# led.net
KiCad netlist of a schematic drawn in EAGLE
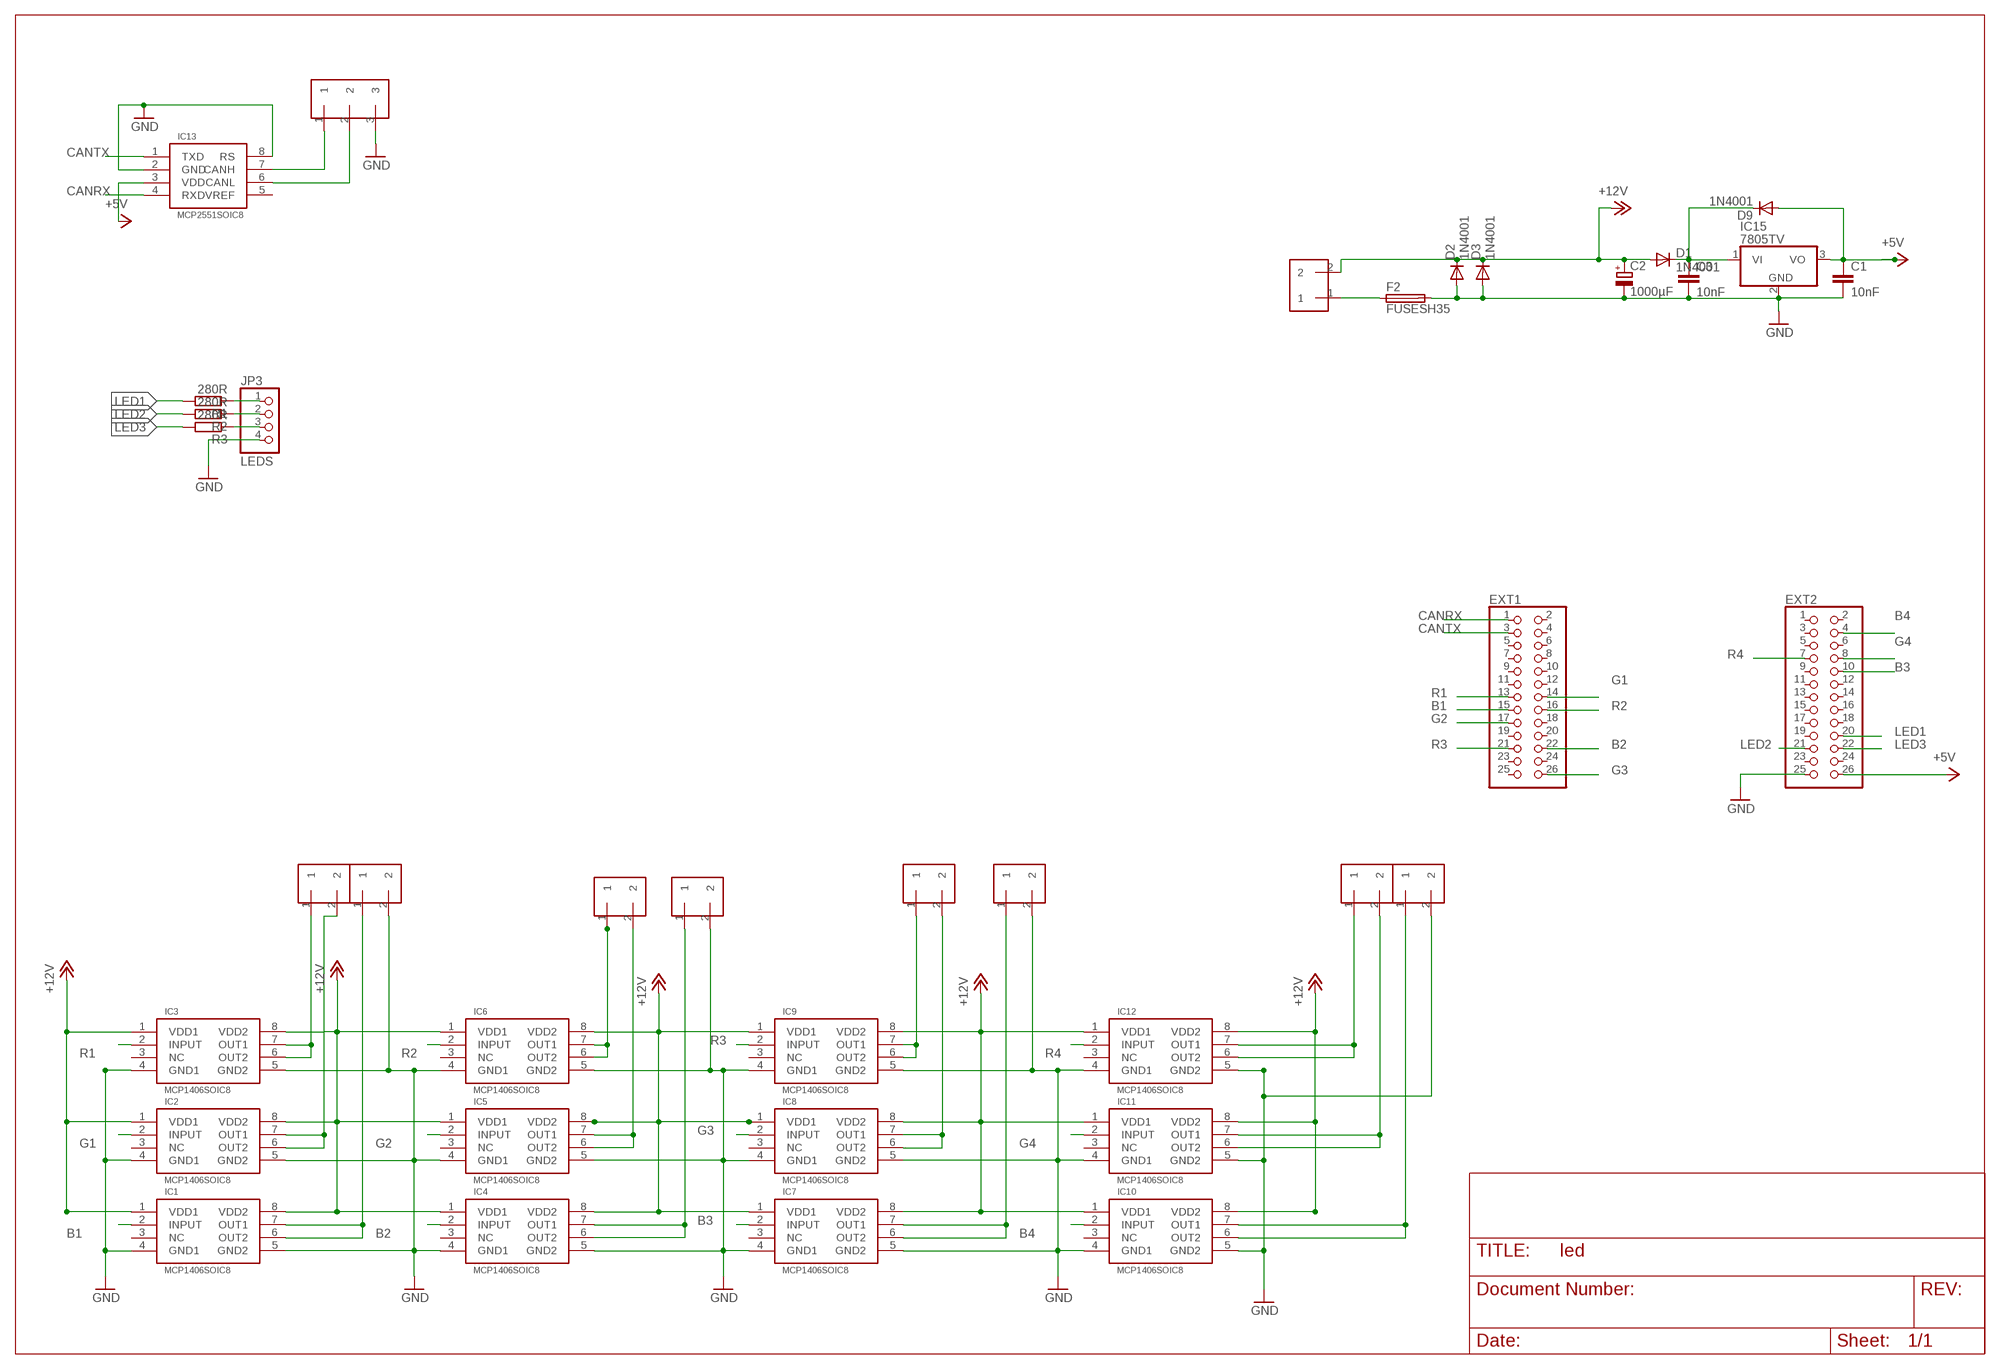
[diagram p0: schematic, sheet 1]

(export (version "E")
  (design (tool "Eeschema 10.0.6"))
  (components
    (comp (ref "C1")
      (value "10nF")
      (footprint "eagle-import:C025-025X050")
      (libsource (lib "eagle-import") (part "C-EU025-025X050"))
    )
    (comp (ref "C2")
      (value "1000µF")
      (footprint "eagle-import:E5-8,5")
      (libsource (lib "eagle-import") (part "CPOL-EUE5-8.5"))
    )
    (comp (ref "C3")
      (value "10nF")
      (footprint "eagle-import:C025-025X050")
      (libsource (lib "eagle-import") (part "C-EU025-025X050"))
    )
    (comp (ref "D1")
      (value "1N4001")
      (footprint "eagle-import:MELF-MLL41")
      (libsource (lib "eagle-import") (part "DIODE-MELF-MLL41"))
    )
    (comp (ref "D2")
      (value "1N4001")
      (footprint "eagle-import:MELF-MLL41")
      (libsource (lib "eagle-import") (part "DIODE-MELF-MLL41"))
    )
    (comp (ref "D3")
      (value "1N4001")
      (footprint "eagle-import:MELF-MLL41")
      (libsource (lib "eagle-import") (part "DIODE-MELF-MLL41"))
    )
    (comp (ref "D9")
      (value "1N4001")
      (footprint "eagle-import:MELF-MLL41")
      (libsource (lib "eagle-import") (part "DIODE-MELF-MLL41"))
    )
    (comp (ref "EXT1")
      (value "PINHD-2X13")
      (footprint "eagle-import:2X13")
      (libsource (lib "eagle-import") (part "PINHD-2X13"))
    )
    (comp (ref "EXT2")
      (value "PINHD-2X13")
      (footprint "eagle-import:2X13")
      (libsource (lib "eagle-import") (part "PINHD-2X13"))
    )
    (comp (ref "F2")
      (value "FUSESH35")
      (footprint "eagle-import:SH25")
      (libsource (lib "eagle-import") (part "FUSESH35"))
    )
    (comp (ref "IC1")
      (value "MCP1406SOIC8")
      (footprint "eagle-import:SOIC-08LG")
      (libsource (lib "eagle-import") (part "MCP1406SOIC8"))
    )
    (comp (ref "IC2")
      (value "MCP1406SOIC8")
      (footprint "eagle-import:SOIC-08LG")
      (libsource (lib "eagle-import") (part "MCP1406SOIC8"))
    )
    (comp (ref "IC3")
      (value "MCP1406SOIC8")
      (footprint "eagle-import:SOIC-08LG")
      (libsource (lib "eagle-import") (part "MCP1406SOIC8"))
    )
    (comp (ref "IC4")
      (value "MCP1406SOIC8")
      (footprint "eagle-import:SOIC-08LG")
      (libsource (lib "eagle-import") (part "MCP1406SOIC8"))
    )
    (comp (ref "IC5")
      (value "MCP1406SOIC8")
      (footprint "eagle-import:SOIC-08LG")
      (libsource (lib "eagle-import") (part "MCP1406SOIC8"))
    )
    (comp (ref "IC6")
      (value "MCP1406SOIC8")
      (footprint "eagle-import:SOIC-08LG")
      (libsource (lib "eagle-import") (part "MCP1406SOIC8"))
    )
    (comp (ref "IC7")
      (value "MCP1406SOIC8")
      (footprint "eagle-import:SOIC-08LG")
      (libsource (lib "eagle-import") (part "MCP1406SOIC8"))
    )
    (comp (ref "IC8")
      (value "MCP1406SOIC8")
      (footprint "eagle-import:SOIC-08LG")
      (libsource (lib "eagle-import") (part "MCP1406SOIC8"))
    )
    (comp (ref "IC9")
      (value "MCP1406SOIC8")
      (footprint "eagle-import:SOIC-08LG")
      (libsource (lib "eagle-import") (part "MCP1406SOIC8"))
    )
    (comp (ref "IC10")
      (value "MCP1406SOIC8")
      (footprint "eagle-import:SOIC-08LG")
      (libsource (lib "eagle-import") (part "MCP1406SOIC8"))
    )
    (comp (ref "IC11")
      (value "MCP1406SOIC8")
      (footprint "eagle-import:SOIC-08LG")
      (libsource (lib "eagle-import") (part "MCP1406SOIC8"))
    )
    (comp (ref "IC12")
      (value "MCP1406SOIC8")
      (footprint "eagle-import:SOIC-08LG")
      (libsource (lib "eagle-import") (part "MCP1406SOIC8"))
    )
    (comp (ref "IC13")
      (value "MCP2551SOIC8")
      (footprint "eagle-import:SOIC-08LG")
      (libsource (lib "eagle-import") (part "MCP2551SOIC8"))
    )
    (comp (ref "IC15")
      (value "7805TV")
      (footprint "eagle-import:TO220V")
      (libsource (lib "eagle-import") (part "78TV05"))
    )
    (comp (ref "JP3")
      (value "LEDS")
      (footprint "eagle-import:1X04")
      (libsource (lib "eagle-import") (part "PINHD-1X4"))
    )
    (comp (ref "R1")
      (value "280R")
      (footprint "eagle-import:0204_7")
      (libsource (lib "eagle-import") (part "R-EU_0204/7"))
    )
    (comp (ref "R2")
      (value "280R")
      (footprint "eagle-import:0204_7")
      (libsource (lib "eagle-import") (part "R-EU_0204/7"))
    )
    (comp (ref "R3")
      (value "280R")
      (footprint "eagle-import:0204_7")
      (libsource (lib "eagle-import") (part "R-EU_0204/7"))
    )
    (comp (ref "U$1")
      (value "2KLEMME")
      (footprint "eagle-import:W237-102")
      (libsource (lib "eagle-import") (part "2KLEMME"))
    )
    (comp (ref "U$2")
      (value "2KLEMME")
      (footprint "eagle-import:W237-102")
      (libsource (lib "eagle-import") (part "2KLEMME"))
    )
    (comp (ref "U$3")
      (value "3KLEMME")
      (footprint "eagle-import:W237-103")
      (libsource (lib "eagle-import") (part "3KLEMME"))
    )
    (comp (ref "U$5")
      (value "2KLEMME")
      (footprint "eagle-import:W237-102")
      (libsource (lib "eagle-import") (part "2KLEMME"))
    )
    (comp (ref "U$6")
      (value "2KLEMME")
      (footprint "eagle-import:W237-102")
      (libsource (lib "eagle-import") (part "2KLEMME"))
    )
    (comp (ref "U$7")
      (value "2KLEMME")
      (footprint "eagle-import:W237-102")
      (libsource (lib "eagle-import") (part "2KLEMME"))
    )
    (comp (ref "U$8")
      (value "2KLEMME")
      (footprint "eagle-import:W237-102")
      (libsource (lib "eagle-import") (part "2KLEMME"))
    )
    (comp (ref "U$9")
      (value "2KLEMME")
      (footprint "eagle-import:W237-102")
      (libsource (lib "eagle-import") (part "2KLEMME"))
    )
    (comp (ref "U$10")
      (value "2KLEMME")
      (footprint "eagle-import:W237-102")
      (libsource (lib "eagle-import") (part "2KLEMME"))
    )
    (comp (ref "U$11")
      (value "2KLEMME")
      (footprint "eagle-import:W237-102")
      (libsource (lib "eagle-import") (part "2KLEMME"))
    )
  )
  (nets
    (net (code "1") (name "+5V") (class "Default")
      (node (ref "C1") (pin "1") (pinfunction "1_1") (pintype "passive"))
      (node (ref "D9") (pin "A") (pinfunction "A_A") (pintype "passive"))
      (node (ref "EXT2") (pin "26") (pinfunction "26_26") (pintype "passive"))
      (node (ref "IC13") (pin "3") (pinfunction "VDD_3") (pintype "bidirectional"))
      (node (ref "IC15") (pin "3") (pinfunction "VO_3") (pintype "passive"))
    )
    (net (code "2") (name "+12V") (class "Default")
      (node (ref "C2") (pin "+") (pinfunction "+_+") (pintype "passive"))
      (node (ref "D1") (pin "A") (pinfunction "A_A") (pintype "passive"))
      (node (ref "D2") (pin "C") (pinfunction "C_C") (pintype "passive"))
      (node (ref "D3") (pin "C") (pinfunction "C_C") (pintype "passive"))
      (node (ref "IC1") (pin "1") (pinfunction "VDD1_1") (pintype "bidirectional"))
      (node (ref "IC1") (pin "8") (pinfunction "VDD2_8") (pintype "bidirectional"))
      (node (ref "IC10") (pin "1") (pinfunction "VDD1_1") (pintype "bidirectional"))
      (node (ref "IC10") (pin "8") (pinfunction "VDD2_8") (pintype "bidirectional"))
      (node (ref "IC11") (pin "1") (pinfunction "VDD1_1") (pintype "bidirectional"))
      (node (ref "IC11") (pin "8") (pinfunction "VDD2_8") (pintype "bidirectional"))
      (node (ref "IC12") (pin "1") (pinfunction "VDD1_1") (pintype "bidirectional"))
      (node (ref "IC12") (pin "8") (pinfunction "VDD2_8") (pintype "bidirectional"))
      (node (ref "IC2") (pin "1") (pinfunction "VDD1_1") (pintype "bidirectional"))
      (node (ref "IC2") (pin "8") (pinfunction "VDD2_8") (pintype "bidirectional"))
      (node (ref "IC3") (pin "1") (pinfunction "VDD1_1") (pintype "bidirectional"))
      (node (ref "IC3") (pin "8") (pinfunction "VDD2_8") (pintype "bidirectional"))
      (node (ref "IC4") (pin "1") (pinfunction "VDD1_1") (pintype "bidirectional"))
      (node (ref "IC4") (pin "8") (pinfunction "VDD2_8") (pintype "bidirectional"))
      (node (ref "IC5") (pin "1") (pinfunction "VDD1_1") (pintype "bidirectional"))
      (node (ref "IC5") (pin "8") (pinfunction "VDD2_8") (pintype "bidirectional"))
      (node (ref "IC6") (pin "1") (pinfunction "VDD1_1") (pintype "bidirectional"))
      (node (ref "IC6") (pin "8") (pinfunction "VDD2_8") (pintype "bidirectional"))
      (node (ref "IC7") (pin "1") (pinfunction "VDD1_1") (pintype "bidirectional"))
      (node (ref "IC7") (pin "8") (pinfunction "VDD2_8") (pintype "bidirectional"))
      (node (ref "IC8") (pin "1") (pinfunction "VDD1_1") (pintype "bidirectional"))
      (node (ref "IC8") (pin "8") (pinfunction "VDD2_8") (pintype "bidirectional"))
      (node (ref "IC9") (pin "1") (pinfunction "VDD1_1") (pintype "bidirectional"))
      (node (ref "IC9") (pin "8") (pinfunction "VDD2_8") (pintype "bidirectional"))
      (node (ref "U$1") (pin "2") (pinfunction "2_2") (pintype "bidirectional"))
    )
    (net (code "3") (name "/B1") (class "Default")
      (node (ref "EXT1") (pin "15") (pinfunction "15_15") (pintype "passive"))
      (node (ref "IC1") (pin "2") (pinfunction "INPUT_2") (pintype "bidirectional"))
    )
    (net (code "4") (name "/B2") (class "Default")
      (node (ref "EXT1") (pin "22") (pinfunction "22_22") (pintype "passive"))
      (node (ref "IC4") (pin "2") (pinfunction "INPUT_2") (pintype "bidirectional"))
    )
    (net (code "5") (name "/B3") (class "Default")
      (node (ref "EXT2") (pin "10") (pinfunction "10_10") (pintype "passive"))
      (node (ref "IC7") (pin "2") (pinfunction "INPUT_2") (pintype "bidirectional"))
    )
    (net (code "6") (name "/B4") (class "Default")
      (node (ref "EXT2") (pin "4") (pinfunction "4_4") (pintype "passive"))
      (node (ref "IC10") (pin "2") (pinfunction "INPUT_2") (pintype "bidirectional"))
    )
    (net (code "7") (name "/CANRX") (class "Default")
      (node (ref "EXT1") (pin "1") (pinfunction "1_1") (pintype "passive"))
      (node (ref "IC13") (pin "4") (pinfunction "RXD_4") (pintype "bidirectional"))
    )
    (net (code "8") (name "/CANTX") (class "Default")
      (node (ref "EXT1") (pin "3") (pinfunction "3_3") (pintype "passive"))
      (node (ref "IC13") (pin "1") (pinfunction "TXD_1") (pintype "bidirectional"))
    )
    (net (code "9") (name "/G1") (class "Default")
      (node (ref "EXT1") (pin "14") (pinfunction "14_14") (pintype "passive"))
      (node (ref "IC2") (pin "2") (pinfunction "INPUT_2") (pintype "bidirectional"))
    )
    (net (code "10") (name "/G2") (class "Default")
      (node (ref "EXT1") (pin "17") (pinfunction "17_17") (pintype "passive"))
      (node (ref "IC5") (pin "2") (pinfunction "INPUT_2") (pintype "bidirectional"))
    )
    (net (code "11") (name "/G3") (class "Default")
      (node (ref "EXT1") (pin "26") (pinfunction "26_26") (pintype "passive"))
      (node (ref "IC8") (pin "2") (pinfunction "INPUT_2") (pintype "bidirectional"))
    )
    (net (code "12") (name "/G4") (class "Default")
      (node (ref "EXT2") (pin "8") (pinfunction "8_8") (pintype "passive"))
      (node (ref "IC11") (pin "2") (pinfunction "INPUT_2") (pintype "bidirectional"))
    )
    (net (code "13") (name "/R1") (class "Default")
      (node (ref "EXT1") (pin "13") (pinfunction "13_13") (pintype "passive"))
      (node (ref "IC3") (pin "2") (pinfunction "INPUT_2") (pintype "bidirectional"))
    )
    (net (code "14") (name "/R2") (class "Default")
      (node (ref "EXT1") (pin "16") (pinfunction "16_16") (pintype "passive"))
      (node (ref "IC6") (pin "2") (pinfunction "INPUT_2") (pintype "bidirectional"))
    )
    (net (code "15") (name "/R3") (class "Default")
      (node (ref "EXT1") (pin "21") (pinfunction "21_21") (pintype "passive"))
      (node (ref "IC9") (pin "2") (pinfunction "INPUT_2") (pintype "bidirectional"))
    )
    (net (code "16") (name "/R4") (class "Default")
      (node (ref "EXT2") (pin "7") (pinfunction "7_7") (pintype "passive"))
      (node (ref "IC12") (pin "2") (pinfunction "INPUT_2") (pintype "bidirectional"))
    )
    (net (code "17") (name "GND") (class "Default")
      (node (ref "C1") (pin "2") (pinfunction "2_2") (pintype "passive"))
      (node (ref "C2") (pin "-") (pinfunction "-_-") (pintype "passive"))
      (node (ref "C3") (pin "2") (pinfunction "2_2") (pintype "passive"))
      (node (ref "D2") (pin "A") (pinfunction "A_A") (pintype "passive"))
      (node (ref "D3") (pin "A") (pinfunction "A_A") (pintype "passive"))
      (node (ref "EXT2") (pin "25") (pinfunction "25_25") (pintype "passive"))
      (node (ref "F2") (pin "2") (pinfunction "2_2") (pintype "passive"))
      (node (ref "IC1") (pin "4") (pinfunction "GND1_4") (pintype "bidirectional"))
      (node (ref "IC1") (pin "5") (pinfunction "GND2_5") (pintype "bidirectional"))
      (node (ref "IC10") (pin "4") (pinfunction "GND1_4") (pintype "bidirectional"))
      (node (ref "IC10") (pin "5") (pinfunction "GND2_5") (pintype "bidirectional"))
      (node (ref "IC11") (pin "4") (pinfunction "GND1_4") (pintype "bidirectional"))
      (node (ref "IC11") (pin "5") (pinfunction "GND2_5") (pintype "bidirectional"))
      (node (ref "IC12") (pin "4") (pinfunction "GND1_4") (pintype "bidirectional"))
      (node (ref "IC12") (pin "5") (pinfunction "GND2_5") (pintype "bidirectional"))
      (node (ref "IC13") (pin "2") (pinfunction "GND_2") (pintype "bidirectional"))
      (node (ref "IC13") (pin "8") (pinfunction "RS_8") (pintype "bidirectional"))
      (node (ref "IC15") (pin "2") (pinfunction "GND_2") (pintype "passive"))
      (node (ref "IC2") (pin "4") (pinfunction "GND1_4") (pintype "bidirectional"))
      (node (ref "IC2") (pin "5") (pinfunction "GND2_5") (pintype "bidirectional"))
      (node (ref "IC3") (pin "4") (pinfunction "GND1_4") (pintype "bidirectional"))
      (node (ref "IC3") (pin "5") (pinfunction "GND2_5") (pintype "bidirectional"))
      (node (ref "IC4") (pin "4") (pinfunction "GND1_4") (pintype "bidirectional"))
      (node (ref "IC4") (pin "5") (pinfunction "GND2_5") (pintype "bidirectional"))
      (node (ref "IC5") (pin "4") (pinfunction "GND1_4") (pintype "bidirectional"))
      (node (ref "IC5") (pin "5") (pinfunction "GND2_5") (pintype "bidirectional"))
      (node (ref "IC6") (pin "4") (pinfunction "GND1_4") (pintype "bidirectional"))
      (node (ref "IC6") (pin "5") (pinfunction "GND2_5") (pintype "bidirectional"))
      (node (ref "IC7") (pin "4") (pinfunction "GND1_4") (pintype "bidirectional"))
      (node (ref "IC7") (pin "5") (pinfunction "GND2_5") (pintype "bidirectional"))
      (node (ref "IC8") (pin "4") (pinfunction "GND1_4") (pintype "bidirectional"))
      (node (ref "IC8") (pin "5") (pinfunction "GND2_5") (pintype "bidirectional"))
      (node (ref "IC9") (pin "4") (pinfunction "GND1_4") (pintype "bidirectional"))
      (node (ref "IC9") (pin "5") (pinfunction "GND2_5") (pintype "bidirectional"))
      (node (ref "JP3") (pin "4") (pinfunction "4_4") (pintype "passive"))
      (node (ref "U$11") (pin "2") (pinfunction "2_2") (pintype "bidirectional"))
      (node (ref "U$2") (pin "2") (pinfunction "2_2") (pintype "bidirectional"))
      (node (ref "U$3") (pin "3") (pinfunction "3_3") (pintype "bidirectional"))
      (node (ref "U$6") (pin "2") (pinfunction "2_2") (pintype "bidirectional"))
      (node (ref "U$7") (pin "2") (pinfunction "2_2") (pintype "bidirectional"))
    )
    (net (code "18") (name "LED1") (class "Default")
      (node (ref "EXT2") (pin "20") (pinfunction "20_20") (pintype "passive"))
      (node (ref "R1") (pin "2") (pinfunction "2_2") (pintype "passive"))
    )
    (net (code "19") (name "LED2") (class "Default")
      (node (ref "EXT2") (pin "21") (pinfunction "21_21") (pintype "passive"))
      (node (ref "R2") (pin "2") (pinfunction "2_2") (pintype "passive"))
    )
    (net (code "20") (name "LED3") (class "Default")
      (node (ref "EXT2") (pin "22") (pinfunction "22_22") (pintype "passive"))
      (node (ref "R3") (pin "2") (pinfunction "2_2") (pintype "passive"))
    )
    (net (code "21") (name "Net-(F2-Pad1)") (class "Default")
      (node (ref "F2") (pin "1") (pinfunction "1_1") (pintype "passive"))
      (node (ref "U$1") (pin "1") (pinfunction "1_1") (pintype "bidirectional"))
    )
    (net (code "22") (name "Net-(IC1-OUT1)") (class "Default")
      (node (ref "IC1") (pin "6") (pinfunction "OUT2_6") (pintype "bidirectional"))
      (node (ref "IC1") (pin "7") (pinfunction "OUT1_7") (pintype "bidirectional"))
      (node (ref "U$6") (pin "1") (pinfunction "1_1") (pintype "bidirectional"))
    )
    (net (code "23") (name "Net-(IC2-OUT1)") (class "Default")
      (node (ref "IC2") (pin "6") (pinfunction "OUT2_6") (pintype "bidirectional"))
      (node (ref "IC2") (pin "7") (pinfunction "OUT1_7") (pintype "bidirectional"))
      (node (ref "U$5") (pin "2") (pinfunction "2_2") (pintype "bidirectional"))
    )
    (net (code "24") (name "Net-(IC3-OUT1)") (class "Default")
      (node (ref "IC3") (pin "6") (pinfunction "OUT2_6") (pintype "bidirectional"))
      (node (ref "IC3") (pin "7") (pinfunction "OUT1_7") (pintype "bidirectional"))
      (node (ref "U$5") (pin "1") (pinfunction "1_1") (pintype "bidirectional"))
    )
    (net (code "25") (name "Net-(IC4-OUT1)") (class "Default")
      (node (ref "IC4") (pin "6") (pinfunction "OUT2_6") (pintype "bidirectional"))
      (node (ref "IC4") (pin "7") (pinfunction "OUT1_7") (pintype "bidirectional"))
      (node (ref "U$11") (pin "1") (pinfunction "1_1") (pintype "bidirectional"))
    )
    (net (code "26") (name "Net-(IC5-OUT1)") (class "Default")
      (node (ref "IC5") (pin "6") (pinfunction "OUT2_6") (pintype "bidirectional"))
      (node (ref "IC5") (pin "7") (pinfunction "OUT1_7") (pintype "bidirectional"))
      (node (ref "U$10") (pin "2") (pinfunction "2_2") (pintype "bidirectional"))
    )
    (net (code "27") (name "Net-(IC6-OUT1)") (class "Default")
      (node (ref "IC6") (pin "6") (pinfunction "OUT2_6") (pintype "bidirectional"))
      (node (ref "IC6") (pin "7") (pinfunction "OUT1_7") (pintype "bidirectional"))
      (node (ref "U$10") (pin "1") (pinfunction "1_1") (pintype "bidirectional"))
    )
    (net (code "28") (name "Net-(IC7-OUT1)") (class "Default")
      (node (ref "IC7") (pin "6") (pinfunction "OUT2_6") (pintype "bidirectional"))
      (node (ref "IC7") (pin "7") (pinfunction "OUT1_7") (pintype "bidirectional"))
      (node (ref "U$7") (pin "1") (pinfunction "1_1") (pintype "bidirectional"))
    )
    (net (code "29") (name "Net-(IC8-OUT1)") (class "Default")
      (node (ref "IC8") (pin "6") (pinfunction "OUT2_6") (pintype "bidirectional"))
      (node (ref "IC8") (pin "7") (pinfunction "OUT1_7") (pintype "bidirectional"))
      (node (ref "U$8") (pin "2") (pinfunction "2_2") (pintype "bidirectional"))
    )
    (net (code "30") (name "Net-(IC9-OUT1)") (class "Default")
      (node (ref "IC9") (pin "6") (pinfunction "OUT2_6") (pintype "bidirectional"))
      (node (ref "IC9") (pin "7") (pinfunction "OUT1_7") (pintype "bidirectional"))
      (node (ref "U$8") (pin "1") (pinfunction "1_1") (pintype "bidirectional"))
    )
    (net (code "31") (name "Net-(IC10-OUT1)") (class "Default")
      (node (ref "IC10") (pin "6") (pinfunction "OUT2_6") (pintype "bidirectional"))
      (node (ref "IC10") (pin "7") (pinfunction "OUT1_7") (pintype "bidirectional"))
      (node (ref "U$2") (pin "1") (pinfunction "1_1") (pintype "bidirectional"))
    )
    (net (code "32") (name "Net-(IC11-OUT1)") (class "Default")
      (node (ref "IC11") (pin "6") (pinfunction "OUT2_6") (pintype "bidirectional"))
      (node (ref "IC11") (pin "7") (pinfunction "OUT1_7") (pintype "bidirectional"))
      (node (ref "U$9") (pin "2") (pinfunction "2_2") (pintype "bidirectional"))
    )
    (net (code "33") (name "Net-(IC12-OUT1)") (class "Default")
      (node (ref "IC12") (pin "6") (pinfunction "OUT2_6") (pintype "bidirectional"))
      (node (ref "IC12") (pin "7") (pinfunction "OUT1_7") (pintype "bidirectional"))
      (node (ref "U$9") (pin "1") (pinfunction "1_1") (pintype "bidirectional"))
    )
    (net (code "34") (name "Net-(IC13-CANH)") (class "Default")
      (node (ref "IC13") (pin "7") (pinfunction "CANH_7") (pintype "bidirectional"))
      (node (ref "U$3") (pin "1") (pinfunction "1_1") (pintype "bidirectional"))
    )
    (net (code "35") (name "Net-(IC13-CANL)") (class "Default")
      (node (ref "IC13") (pin "6") (pinfunction "CANL_6") (pintype "bidirectional"))
      (node (ref "U$3") (pin "2") (pinfunction "2_2") (pintype "bidirectional"))
    )
    (net (code "36") (name "Net-(IC15-VI)") (class "Default")
      (node (ref "C3") (pin "1") (pinfunction "1_1") (pintype "passive"))
      (node (ref "D1") (pin "C") (pinfunction "C_C") (pintype "passive"))
      (node (ref "D9") (pin "C") (pinfunction "C_C") (pintype "passive"))
      (node (ref "IC15") (pin "1") (pinfunction "VI_1") (pintype "input"))
    )
    (net (code "37") (name "Net-(JP3-Pad1)") (class "Default")
      (node (ref "JP3") (pin "1") (pinfunction "1_1") (pintype "passive"))
      (node (ref "R1") (pin "1") (pinfunction "1_1") (pintype "passive"))
    )
    (net (code "38") (name "Net-(JP3-Pad2)") (class "Default")
      (node (ref "JP3") (pin "2") (pinfunction "2_2") (pintype "passive"))
      (node (ref "R2") (pin "1") (pinfunction "1_1") (pintype "passive"))
    )
    (net (code "39") (name "Net-(JP3-Pad3)") (class "Default")
      (node (ref "JP3") (pin "3") (pinfunction "3_3") (pintype "passive"))
      (node (ref "R3") (pin "1") (pinfunction "1_1") (pintype "passive"))
    )
    (net (code "40") (name "unconnected-(EXT1-Pad2)") (class "Default")
      (node (ref "EXT1") (pin "2") (pinfunction "2_2") (pintype "passive"))
    )
    (net (code "41") (name "unconnected-(EXT1-Pad4)") (class "Default")
      (node (ref "EXT1") (pin "4") (pinfunction "4_4") (pintype "passive"))
    )
    (net (code "42") (name "unconnected-(EXT1-Pad5)") (class "Default")
      (node (ref "EXT1") (pin "5") (pinfunction "5_5") (pintype "passive"))
    )
    (net (code "43") (name "unconnected-(EXT1-Pad6)") (class "Default")
      (node (ref "EXT1") (pin "6") (pinfunction "6_6") (pintype "passive"))
    )
    (net (code "44") (name "unconnected-(EXT1-Pad7)") (class "Default")
      (node (ref "EXT1") (pin "7") (pinfunction "7_7") (pintype "passive"))
    )
    (net (code "45") (name "unconnected-(EXT1-Pad8)") (class "Default")
      (node (ref "EXT1") (pin "8") (pinfunction "8_8") (pintype "passive"))
    )
    (net (code "46") (name "unconnected-(EXT1-Pad9)") (class "Default")
      (node (ref "EXT1") (pin "9") (pinfunction "9_9") (pintype "passive"))
    )
    (net (code "47") (name "unconnected-(EXT1-Pad10)") (class "Default")
      (node (ref "EXT1") (pin "10") (pinfunction "10_10") (pintype "passive"))
    )
    (net (code "48") (name "unconnected-(EXT1-Pad11)") (class "Default")
      (node (ref "EXT1") (pin "11") (pinfunction "11_11") (pintype "passive"))
    )
    (net (code "49") (name "unconnected-(EXT1-Pad12)") (class "Default")
      (node (ref "EXT1") (pin "12") (pinfunction "12_12") (pintype "passive"))
    )
    (net (code "50") (name "unconnected-(EXT1-Pad18)") (class "Default")
      (node (ref "EXT1") (pin "18") (pinfunction "18_18") (pintype "passive"))
    )
    (net (code "51") (name "unconnected-(EXT1-Pad19)") (class "Default")
      (node (ref "EXT1") (pin "19") (pinfunction "19_19") (pintype "passive"))
    )
    (net (code "52") (name "unconnected-(EXT1-Pad20)") (class "Default")
      (node (ref "EXT1") (pin "20") (pinfunction "20_20") (pintype "passive"))
    )
    (net (code "53") (name "unconnected-(EXT1-Pad23)") (class "Default")
      (node (ref "EXT1") (pin "23") (pinfunction "23_23") (pintype "passive"))
    )
    (net (code "54") (name "unconnected-(EXT1-Pad24)") (class "Default")
      (node (ref "EXT1") (pin "24") (pinfunction "24_24") (pintype "passive"))
    )
    (net (code "55") (name "unconnected-(EXT1-Pad25)") (class "Default")
      (node (ref "EXT1") (pin "25") (pinfunction "25_25") (pintype "passive"))
    )
    (net (code "56") (name "unconnected-(EXT2-Pad1)") (class "Default")
      (node (ref "EXT2") (pin "1") (pinfunction "1_1") (pintype "passive"))
    )
    (net (code "57") (name "unconnected-(EXT2-Pad2)") (class "Default")
      (node (ref "EXT2") (pin "2") (pinfunction "2_2") (pintype "passive"))
    )
    (net (code "58") (name "unconnected-(EXT2-Pad3)") (class "Default")
      (node (ref "EXT2") (pin "3") (pinfunction "3_3") (pintype "passive"))
    )
    (net (code "59") (name "unconnected-(EXT2-Pad5)") (class "Default")
      (node (ref "EXT2") (pin "5") (pinfunction "5_5") (pintype "passive"))
    )
    (net (code "60") (name "unconnected-(EXT2-Pad6)") (class "Default")
      (node (ref "EXT2") (pin "6") (pinfunction "6_6") (pintype "passive"))
    )
    (net (code "61") (name "unconnected-(EXT2-Pad9)") (class "Default")
      (node (ref "EXT2") (pin "9") (pinfunction "9_9") (pintype "passive"))
    )
    (net (code "62") (name "unconnected-(EXT2-Pad11)") (class "Default")
      (node (ref "EXT2") (pin "11") (pinfunction "11_11") (pintype "passive"))
    )
    (net (code "63") (name "unconnected-(EXT2-Pad12)") (class "Default")
      (node (ref "EXT2") (pin "12") (pinfunction "12_12") (pintype "passive"))
    )
    (net (code "64") (name "unconnected-(EXT2-Pad13)") (class "Default")
      (node (ref "EXT2") (pin "13") (pinfunction "13_13") (pintype "passive"))
    )
    (net (code "65") (name "unconnected-(EXT2-Pad14)") (class "Default")
      (node (ref "EXT2") (pin "14") (pinfunction "14_14") (pintype "passive"))
    )
    (net (code "66") (name "unconnected-(EXT2-Pad15)") (class "Default")
      (node (ref "EXT2") (pin "15") (pinfunction "15_15") (pintype "passive"))
    )
    (net (code "67") (name "unconnected-(EXT2-Pad16)") (class "Default")
      (node (ref "EXT2") (pin "16") (pinfunction "16_16") (pintype "passive"))
    )
    (net (code "68") (name "unconnected-(EXT2-Pad17)") (class "Default")
      (node (ref "EXT2") (pin "17") (pinfunction "17_17") (pintype "passive"))
    )
    (net (code "69") (name "unconnected-(EXT2-Pad18)") (class "Default")
      (node (ref "EXT2") (pin "18") (pinfunction "18_18") (pintype "passive"))
    )
    (net (code "70") (name "unconnected-(EXT2-Pad19)") (class "Default")
      (node (ref "EXT2") (pin "19") (pinfunction "19_19") (pintype "passive"))
    )
    (net (code "71") (name "unconnected-(EXT2-Pad23)") (class "Default")
      (node (ref "EXT2") (pin "23") (pinfunction "23_23") (pintype "passive"))
    )
    (net (code "72") (name "unconnected-(EXT2-Pad24)") (class "Default")
      (node (ref "EXT2") (pin "24") (pinfunction "24_24") (pintype "passive"))
    )
    (net (code "73") (name "unconnected-(IC1-NC-Pad3)") (class "Default")
      (node (ref "IC1") (pin "3") (pinfunction "NC_3") (pintype "bidirectional"))
    )
    (net (code "74") (name "unconnected-(IC2-NC-Pad3)") (class "Default")
      (node (ref "IC2") (pin "3") (pinfunction "NC_3") (pintype "bidirectional"))
    )
    (net (code "75") (name "unconnected-(IC3-NC-Pad3)") (class "Default")
      (node (ref "IC3") (pin "3") (pinfunction "NC_3") (pintype "bidirectional"))
    )
    (net (code "76") (name "unconnected-(IC4-NC-Pad3)") (class "Default")
      (node (ref "IC4") (pin "3") (pinfunction "NC_3") (pintype "bidirectional"))
    )
    (net (code "77") (name "unconnected-(IC5-NC-Pad3)") (class "Default")
      (node (ref "IC5") (pin "3") (pinfunction "NC_3") (pintype "bidirectional"))
    )
    (net (code "78") (name "unconnected-(IC6-NC-Pad3)") (class "Default")
      (node (ref "IC6") (pin "3") (pinfunction "NC_3") (pintype "bidirectional"))
    )
    (net (code "79") (name "unconnected-(IC7-NC-Pad3)") (class "Default")
      (node (ref "IC7") (pin "3") (pinfunction "NC_3") (pintype "bidirectional"))
    )
    (net (code "80") (name "unconnected-(IC8-NC-Pad3)") (class "Default")
      (node (ref "IC8") (pin "3") (pinfunction "NC_3") (pintype "bidirectional"))
    )
    (net (code "81") (name "unconnected-(IC9-NC-Pad3)") (class "Default")
      (node (ref "IC9") (pin "3") (pinfunction "NC_3") (pintype "bidirectional"))
    )
    (net (code "82") (name "unconnected-(IC10-NC-Pad3)") (class "Default")
      (node (ref "IC10") (pin "3") (pinfunction "NC_3") (pintype "bidirectional"))
    )
    (net (code "83") (name "unconnected-(IC11-NC-Pad3)") (class "Default")
      (node (ref "IC11") (pin "3") (pinfunction "NC_3") (pintype "bidirectional"))
    )
    (net (code "84") (name "unconnected-(IC12-NC-Pad3)") (class "Default")
      (node (ref "IC12") (pin "3") (pinfunction "NC_3") (pintype "bidirectional"))
    )
    (net (code "85") (name "unconnected-(IC13-VREF-Pad5)") (class "Default")
      (node (ref "IC13") (pin "5") (pinfunction "VREF_5") (pintype "bidirectional"))
    )
  )
)
